# logger2.net
KiCad netlist of a schematic drawn in EAGLE
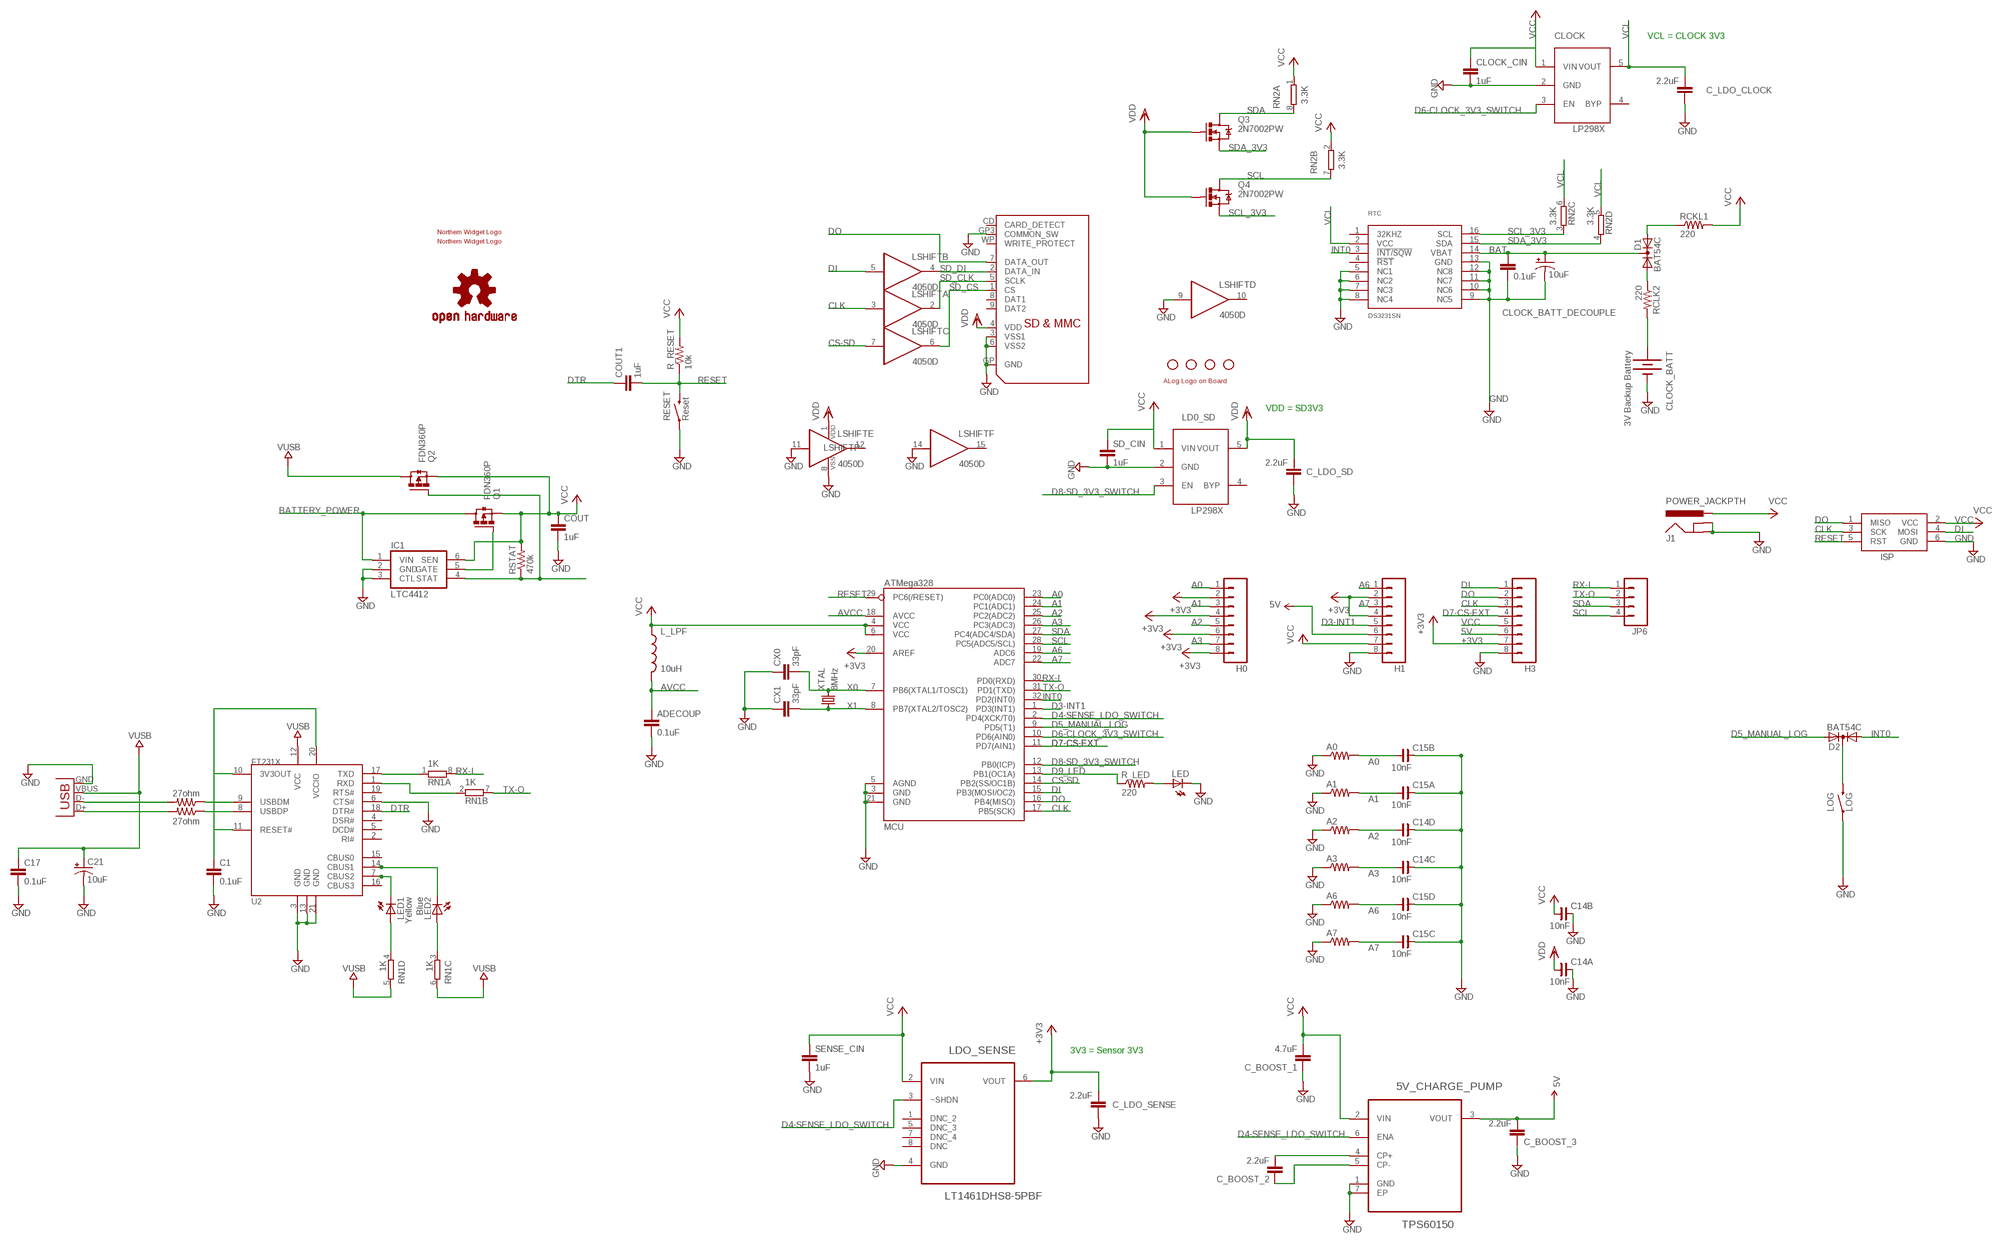
[diagram p0: schematic, sheet 1]

(export (version "E")
  (design (tool "Eeschema 10.0.6"))
  (components
    (comp (ref "5V_CHARGE_PUMP")
      (value "TPS60150")
      (footprint "eagle-import:SON65P200X200X80-7N")
      (fields (field (name "MPN") "TPS60150DRVR"))
      (libsource (lib "eagle-import") (part "TPS60150DRVR"))
    )
    (comp (ref "A0")
      (value "R-US_0207/10")
      (footprint "eagle-import:0207_10")
      (libsource (lib "eagle-import") (part "resistor_R-US_0207/10"))
    )
    (comp (ref "A1")
      (value "R-US_0207/10")
      (footprint "eagle-import:0207_10")
      (libsource (lib "eagle-import") (part "resistor_R-US_0207/10"))
    )
    (comp (ref "A2")
      (value "R-US_0207/10")
      (footprint "eagle-import:0207_10")
      (libsource (lib "eagle-import") (part "resistor_R-US_0207/10"))
    )
    (comp (ref "A3")
      (value "R-US_0207/10")
      (footprint "eagle-import:0207_10")
      (libsource (lib "eagle-import") (part "resistor_R-US_0207/10"))
    )
    (comp (ref "A6")
      (value "R-US_0207/10")
      (footprint "eagle-import:0207_10")
      (libsource (lib "eagle-import") (part "resistor_R-US_0207/10"))
    )
    (comp (ref "A7")
      (value "R-US_0207/10")
      (footprint "eagle-import:0207_10")
      (libsource (lib "eagle-import") (part "resistor_R-US_0207/10"))
    )
    (comp (ref "ADECOUP")
      (value "0.1uF")
      (footprint "eagle-import:C0603")
      (libsource (lib "eagle-import") (part "resistor_C-EUC0603"))
    )
    (comp (ref "C1")
      (value "0.1uF")
      (footprint "eagle-import:C0603")
      (libsource (lib "eagle-import") (part "resistor_C-EUC0603"))
    )
    (comp (ref "C14")
      (value "10nF")
      (footprint "eagle-import:CECJ-1206")
      (libsource (lib "eagle-import") (part "CCA_ECJ-1206"))
    )
    (comp (ref "C15")
      (value "10nF")
      (footprint "eagle-import:CECJ-1206")
      (libsource (lib "eagle-import") (part "CCA_ECJ-1206"))
    )
    (comp (ref "C17")
      (value "0.1uF")
      (footprint "eagle-import:C0603")
      (libsource (lib "eagle-import") (part "resistor_C-EUC0603"))
    )
    (comp (ref "C21")
      (value "10uF")
      (footprint "eagle-import:EIA3216")
      (libsource (lib "eagle-import") (part "CAP_POL1206"))
    )
    (comp (ref "CLOCK")
      (value "LP2985")
      (footprint "eagle-import:SOT23-5L")
      (libsource (lib "eagle-import") (part "LP298XS"))
    )
    (comp (ref "CLOCK_BATT")
      (value "3V Backup Battery")
      (footprint "eagle-import:BATTCON_12MM_PTH")
      (libsource (lib "eagle-import") (part "BATTERY12PTH"))
    )
    (comp (ref "CLOCK_BATT_DECOUP")
      (value "0.1uF")
      (footprint "eagle-import:C0603")
      (libsource (lib "eagle-import") (part "C-EUC0603"))
    )
    (comp (ref "CLOCK_BATT_DECOUPLE")
      (value "10uF")
      (footprint "eagle-import:EIA3216")
      (libsource (lib "eagle-import") (part "CAP_POL1206"))
    )
    (comp (ref "CLOCK_CIN")
      (value "1uF")
      (footprint "eagle-import:C0603")
      (libsource (lib "eagle-import") (part "C-EUC0603"))
    )
    (comp (ref "COUT")
      (value "1uF")
      (footprint "eagle-import:C0603")
      (libsource (lib "eagle-import") (part "C-EUC0603"))
    )
    (comp (ref "COUT1")
      (value "1uF")
      (footprint "eagle-import:C0603")
      (libsource (lib "eagle-import") (part "C-EUC0603"))
    )
    (comp (ref "CX0")
      (value "33pF")
      (footprint "eagle-import:C0603")
      (libsource (lib "eagle-import") (part "resistor_C-EUC0603"))
    )
    (comp (ref "CX1")
      (value "33pF")
      (footprint "eagle-import:C0603")
      (libsource (lib "eagle-import") (part "resistor_C-EUC0603"))
    )
    (comp (ref "C_BOOST_1")
      (value "4.7uF")
      (footprint "eagle-import:C0603")
      (libsource (lib "eagle-import") (part "resistor_C-EUC0603"))
    )
    (comp (ref "C_BOOST_2")
      (value "2.2uF")
      (footprint "eagle-import:C0603")
      (libsource (lib "eagle-import") (part "resistor_C-EUC0603"))
    )
    (comp (ref "C_BOOST_3")
      (value "2.2uF")
      (footprint "eagle-import:C0603")
      (libsource (lib "eagle-import") (part "resistor_C-EUC0603"))
    )
    (comp (ref "C_LDO_CLOCK")
      (value "2.2uF")
      (footprint "eagle-import:C0603")
      (libsource (lib "eagle-import") (part "resistor_C-EUC0603"))
    )
    (comp (ref "C_LDO_SD")
      (value "2.2uF")
      (footprint "eagle-import:C0603")
      (libsource (lib "eagle-import") (part "resistor_C-EUC0603"))
    )
    (comp (ref "C_LDO_SENSE")
      (value "2.2uF")
      (footprint "eagle-import:C0603")
      (libsource (lib "eagle-import") (part "resistor_C-EUC0603"))
    )
    (comp (ref "D+")
      (value "27ohm")
      (footprint "eagle-import:R0603")
      (libsource (lib "eagle-import") (part "R-US_R0603"))
    )
    (comp (ref "D-")
      (value "27ohm")
      (footprint "eagle-import:R0603")
      (libsource (lib "eagle-import") (part "R-US_R0603"))
    )
    (comp (ref "D1")
      (value "BAT54C")
      (footprint "eagle-import:SOT23C")
      (libsource (lib "eagle-import") (part "DIODE_AC-CA_"))
    )
    (comp (ref "D2")
      (value "BAT54C")
      (footprint "eagle-import:SOT23C")
      (libsource (lib "eagle-import") (part "DIODE_AC-CA_"))
    )
    (comp (ref "H0")
      (value "M083.5MM-8")
      (footprint "eagle-import:SCREWTERMINAL-3.5MM-8")
      (libsource (lib "eagle-import") (part "M083.5MM-8"))
    )
    (comp (ref "H1")
      (value "M083.5MM-8")
      (footprint "eagle-import:SCREWTERMINAL-3.5MM-8")
      (libsource (lib "eagle-import") (part "M083.5MM-8"))
    )
    (comp (ref "H3")
      (value "M083.5MM-8")
      (footprint "eagle-import:SCREWTERMINAL-3.5MM-8")
      (libsource (lib "eagle-import") (part "M083.5MM-8"))
    )
    (comp (ref "IC1")
      (value "LTC4412")
      (footprint "eagle-import:TSOT23-6")
      (libsource (lib "eagle-import") (part "LTC4412S6E"))
    )
    (comp (ref "ISP")
      (value "AVRISP-6")
      (footprint "eagle-import:AVRISP")
      (libsource (lib "eagle-import") (part "AVRISP-6"))
    )
    (comp (ref "J1")
      (value "POWER_JACKPTH")
      (footprint "eagle-import:POWER_JACK_PTH")
      (libsource (lib "eagle-import") (part "POWER_JACKPTH"))
    )
    (comp (ref "JP1")
      (value "STAND-OFF")
      (footprint "eagle-import:STAND-OFF")
      (libsource (lib "eagle-import") (part "STAND-OFF"))
    )
    (comp (ref "JP2")
      (value "STAND-OFF")
      (footprint "eagle-import:STAND-OFF")
      (libsource (lib "eagle-import") (part "STAND-OFF"))
    )
    (comp (ref "JP3")
      (value "STAND-OFF")
      (footprint "eagle-import:STAND-OFF")
      (libsource (lib "eagle-import") (part "STAND-OFF"))
    )
    (comp (ref "JP4")
      (value "STAND-OFF")
      (footprint "eagle-import:STAND-OFF")
      (libsource (lib "eagle-import") (part "STAND-OFF"))
    )
    (comp (ref "JP5")
      (value "USB-B")
      (footprint "eagle-import:USB-B-PTH")
      (libsource (lib "eagle-import") (part "USBPTH"))
    )
    (comp (ref "JP6")
      (value "M04SCREW")
      (footprint "eagle-import:SCREWTERMINAL-3.5MM-4")
      (libsource (lib "eagle-import") (part "M04SCREW"))
    )
    (comp (ref "LD0_SD")
      (value "LP2985")
      (footprint "eagle-import:SOT23-5L")
      (libsource (lib "eagle-import") (part "LP298XS"))
    )
    (comp (ref "LDO_SENSE")
      (value "LT1461DHS8-5PBF")
      (footprint "eagle-import:SOIC127P600X175-8N")
      (fields (field (name "MPN") "LT1461DHS8-5#PBF"))
      (libsource (lib "eagle-import") (part "LT1461DHS8-5PBF"))
    )
    (comp (ref "LED")
      (value "LED3MM")
      (footprint "eagle-import:LED3MM")
      (libsource (lib "eagle-import") (part "LED3MM"))
    )
    (comp (ref "LED1")
      (value "Yellow")
      (footprint "eagle-import:LED-0603")
      (libsource (lib "eagle-import") (part "SparkFun-LED_LED0603"))
    )
    (comp (ref "LED2")
      (value "Blue")
      (footprint "eagle-import:LED-0603")
      (libsource (lib "eagle-import") (part "SparkFun-LED_LED0603"))
    )
    (comp (ref "LOG")
      (value "LOG")
      (footprint "eagle-import:TACTILE-PTH")
      (libsource (lib "eagle-import") (part "SWITCH-MOMENTARY-2PTH"))
    )
    (comp (ref "LOGO1")
      (value "OSHW-LOGOM")
      (footprint "eagle-import:OSHW-LOGO-M")
      (libsource (lib "eagle-import") (part "OSHW-LOGOM"))
    )
    (comp (ref "LSHIFT")
      (value "4050D")
      (footprint "eagle-import:SO16")
      (libsource (lib "eagle-import") (part "4050D"))
    )
    (comp (ref "L_LPF")
      (value "10uH")
      (footprint "eagle-import:0805")
      (libsource (lib "eagle-import") (part "INDUCTOR0805"))
    )
    (comp (ref "MCU")
      (value "ATMega328")
      (footprint "eagle-import:TQFP32-08")
      (libsource (lib "eagle-import") (part "ATMEGA168"))
    )
    (comp (ref "Q1")
      (value "FDN360P")
      (footprint "eagle-import:SUPER-SOT3")
      (libsource (lib "eagle-import") (part "FDN360P"))
    )
    (comp (ref "Q2")
      (value "FDN360P")
      (footprint "eagle-import:SUPER-SOT3")
      (libsource (lib "eagle-import") (part "FDN360P"))
    )
    (comp (ref "Q3")
      (value "2N7002PW")
      (footprint "eagle-import:SOT323")
      (libsource (lib "eagle-import") (part "MOSFET-NCHANNELSOT323"))
    )
    (comp (ref "Q4")
      (value "2N7002PW")
      (footprint "eagle-import:SOT323")
      (libsource (lib "eagle-import") (part "MOSFET-NCHANNELSOT323"))
    )
    (comp (ref "RCKL1")
      (value "220")
      (footprint "eagle-import:R0603")
      (libsource (lib "eagle-import") (part "R-US_R0603"))
    )
    (comp (ref "RCLK2")
      (value "220")
      (footprint "eagle-import:R0603")
      (libsource (lib "eagle-import") (part "R-US_R0603"))
    )
    (comp (ref "RESET")
      (value "Reset")
      (footprint "eagle-import:TACTILE-PTH")
      (libsource (lib "eagle-import") (part "SWITCH-MOMENTARY-2PTH"))
    )
    (comp (ref "RN1")
      (value "1K")
      (footprint "eagle-import:0603-ARC")
      (libsource (lib "eagle-import") (part "4R-N0603-ARC"))
    )
    (comp (ref "RN2")
      (value "3.3K")
      (footprint "eagle-import:0603-ARC")
      (libsource (lib "eagle-import") (part "4R-N0603-ARC"))
    )
    (comp (ref "RSTAT")
      (value "470k")
      (footprint "eagle-import:R0603")
      (libsource (lib "eagle-import") (part "R-US_R0603"))
    )
    (comp (ref "RTC")
      (value "DS3231SN")
      (footprint "eagle-import:SO16W")
      (libsource (lib "eagle-import") (part "DS3231SN"))
    )
    (comp (ref "R_LED")
      (value "220")
      (footprint "eagle-import:R0603")
      (libsource (lib "eagle-import") (part "resistor_R-US_R0603"))
    )
    (comp (ref "R_RESET")
      (value "10k")
      (footprint "eagle-import:R0603")
      (libsource (lib "eagle-import") (part "R-US_R0603"))
    )
    (comp (ref "SD")
      (value "SDMMC06132")
      (footprint "eagle-import:06132")
      (libsource (lib "eagle-import") (part "SDMMC06132"))
    )
    (comp (ref "SD_CIN")
      (value "1uF")
      (footprint "eagle-import:C0603")
      (libsource (lib "eagle-import") (part "C-EUC0603"))
    )
    (comp (ref "SENSE_CIN")
      (value "1uF")
      (footprint "eagle-import:C0603")
      (libsource (lib "eagle-import") (part "C-EUC0603"))
    )
    (comp (ref "U$1")
      (value "NWLOGO")
      (footprint "eagle-import:NWLOGO")
      (libsource (lib "eagle-import") (part "NWLOGO"))
    )
    (comp (ref "U$2")
      (value "ALOG_LOGO_V1_5.5MM")
      (footprint "eagle-import:ALOG_LOGO_V1_SMALL")
      (libsource (lib "eagle-import") (part "ALOG_LOGO_V1_5.5MM"))
    )
    (comp (ref "U$3")
      (value "NWLOGO_MED")
      (footprint "eagle-import:NWLOGO_MED")
      (libsource (lib "eagle-import") (part "NWLOGO_MED"))
    )
    (comp (ref "U2")
      (value "FT231X-Q")
      (footprint "eagle-import:QFN20")
      (libsource (lib "eagle-import") (part "FT231X-Q"))
    )
    (comp (ref "XTAL")
      (value "8MHz")
      (footprint "eagle-import:HC49U-V")
      (libsource (lib "eagle-import") (part "CRYSTALHC49UV"))
    )
  )
  (nets
    (net (code "1") (name "+3V3") (class "Default")
      (node (ref "C_LDO_SENSE") (pin "2") (pinfunction "2_2") (pintype "passive"))
      (node (ref "H0") (pin "2") (pinfunction "2_2") (pintype "passive"))
      (node (ref "H0") (pin "4") (pinfunction "4_4") (pintype "passive"))
      (node (ref "H0") (pin "6") (pinfunction "6_6") (pintype "passive"))
      (node (ref "H0") (pin "8") (pinfunction "8_8") (pintype "passive"))
      (node (ref "H1") (pin "2") (pinfunction "2_2") (pintype "passive"))
      (node (ref "H1") (pin "4") (pinfunction "4_4") (pintype "passive"))
      (node (ref "H3") (pin "7") (pinfunction "7_7") (pintype "passive"))
      (node (ref "LDO_SENSE") (pin "6") (pinfunction "VOUT_6") (pintype "output"))
      (node (ref "MCU") (pin "20") (pinfunction "AREF_20") (pintype "bidirectional"))
    )
    (net (code "2") (name "/A0") (class "Default")
      (node (ref "A0") (pin "2") (pinfunction "2_2") (pintype "passive"))
      (node (ref "C15") (pin "B1") (pinfunction "1_B1") (pintype "passive"))
      (node (ref "H0") (pin "1") (pinfunction "1_1") (pintype "passive"))
      (node (ref "MCU") (pin "23") (pinfunction "PC0(ADC0)_23") (pintype "bidirectional"))
    )
    (net (code "3") (name "/A1") (class "Default")
      (node (ref "A1") (pin "2") (pinfunction "2_2") (pintype "passive"))
      (node (ref "C15") (pin "A1") (pinfunction "1_A1") (pintype "passive"))
      (node (ref "H0") (pin "3") (pinfunction "3_3") (pintype "passive"))
      (node (ref "MCU") (pin "24") (pinfunction "PC1(ADC1)_24") (pintype "bidirectional"))
    )
    (net (code "4") (name "/A2") (class "Default")
      (node (ref "A2") (pin "2") (pinfunction "2_2") (pintype "passive"))
      (node (ref "C14") (pin "D1") (pinfunction "1_D1") (pintype "passive"))
      (node (ref "H0") (pin "5") (pinfunction "5_5") (pintype "passive"))
      (node (ref "MCU") (pin "25") (pinfunction "PC2(ADC2)_25") (pintype "bidirectional"))
    )
    (net (code "5") (name "/A3") (class "Default")
      (node (ref "A3") (pin "2") (pinfunction "2_2") (pintype "passive"))
      (node (ref "C14") (pin "C1") (pinfunction "1_C1") (pintype "passive"))
      (node (ref "H0") (pin "7") (pinfunction "7_7") (pintype "passive"))
      (node (ref "MCU") (pin "26") (pinfunction "PC3(ADC3)_26") (pintype "bidirectional"))
    )
    (net (code "6") (name "/A6") (class "Default")
      (node (ref "A6") (pin "2") (pinfunction "2_2") (pintype "passive"))
      (node (ref "C15") (pin "D1") (pinfunction "1_D1") (pintype "passive"))
      (node (ref "H1") (pin "1") (pinfunction "1_1") (pintype "passive"))
      (node (ref "MCU") (pin "19") (pinfunction "ADC6_19") (pintype "bidirectional"))
    )
    (net (code "7") (name "/A7") (class "Default")
      (node (ref "A7") (pin "2") (pinfunction "2_2") (pintype "passive"))
      (node (ref "C15") (pin "C1") (pinfunction "1_C1") (pintype "passive"))
      (node (ref "H1") (pin "3") (pinfunction "3_3") (pintype "passive"))
      (node (ref "MCU") (pin "22") (pinfunction "ADC7_22") (pintype "bidirectional"))
    )
    (net (code "8") (name "/AVCC") (class "Default")
      (node (ref "ADECOUP") (pin "1") (pinfunction "1_1") (pintype "passive"))
      (node (ref "L_LPF") (pin "2") (pinfunction "2_2") (pintype "passive"))
      (node (ref "MCU") (pin "18") (pinfunction "AVCC_18") (pintype "bidirectional"))
    )
    (net (code "9") (name "/BAT") (class "Default")
      (node (ref "CLOCK_BATT_DECOUP") (pin "1") (pinfunction "1_1") (pintype "passive"))
      (node (ref "CLOCK_BATT_DECOUPLE") (pin "A") (pinfunction "+_A") (pintype "passive"))
      (node (ref "D1") (pin "3") (pinfunction "K_3") (pintype "passive"))
      (node (ref "RTC") (pin "14") (pinfunction "VBAT_14") (pintype "bidirectional"))
    )
    (net (code "10") (name "/BATTERY_POWER") (class "Default")
      (node (ref "IC1") (pin "1") (pinfunction "VIN_1") (pintype "input"))
      (node (ref "Q1") (pin "3") (pinfunction "D_3") (pintype "passive"))
    )
    (net (code "11") (name "/CLK") (class "Default")
      (node (ref "H3") (pin "3") (pinfunction "3_3") (pintype "passive"))
      (node (ref "ISP") (pin "3") (pinfunction "SCK_3") (pintype "output"))
      (node (ref "LSHIFT") (pin "3") (pinfunction "I_3") (pintype "input"))
      (node (ref "MCU") (pin "17") (pinfunction "PB5(SCK)_17") (pintype "bidirectional"))
    )
    (net (code "12") (name "/CS-SD") (class "Default")
      (node (ref "LSHIFT") (pin "7") (pinfunction "I_7") (pintype "input"))
      (node (ref "MCU") (pin "14") (pinfunction "PB2(SS/OC1B)_14") (pintype "bidirectional"))
    )
    (net (code "13") (name "/D3-INT1") (class "Default")
      (node (ref "H1") (pin "5") (pinfunction "5_5") (pintype "passive"))
      (node (ref "MCU") (pin "1") (pinfunction "PD3(INT1)_1") (pintype "bidirectional"))
    )
    (net (code "14") (name "/D4-SENSE_LDO_SWITCH") (class "Default")
      (node (ref "5V_CHARGE_PUMP") (pin "6") (pinfunction "ENA_6") (pintype "input"))
      (node (ref "LDO_SENSE") (pin "3") (pinfunction "~{SHDN}_3") (pintype "input"))
      (node (ref "MCU") (pin "2") (pinfunction "PD4(XCK/T0)_2") (pintype "bidirectional"))
    )
    (net (code "15") (name "/D5_MANUAL_LOG") (class "Default")
      (node (ref "D2") (pin "2") (pinfunction "A2_2") (pintype "passive"))
      (node (ref "MCU") (pin "9") (pinfunction "PD5(T1)_9") (pintype "bidirectional"))
    )
    (net (code "16") (name "/D6-CLOCK_3V3_SWITCH") (class "Default")
      (node (ref "CLOCK") (pin "3") (pinfunction "EN_3") (pintype "bidirectional"))
      (node (ref "MCU") (pin "10") (pinfunction "PD6(AIN0)_10") (pintype "bidirectional"))
    )
    (net (code "17") (name "/D7-CS-EXT") (class "Default")
      (node (ref "H3") (pin "4") (pinfunction "4_4") (pintype "passive"))
      (node (ref "MCU") (pin "11") (pinfunction "PD7(AIN1)_11") (pintype "bidirectional"))
    )
    (net (code "18") (name "/D8-SD_3V3_SWITCH") (class "Default")
      (node (ref "LD0_SD") (pin "3") (pinfunction "EN_3") (pintype "bidirectional"))
      (node (ref "MCU") (pin "12") (pinfunction "PB0(ICP)_12") (pintype "bidirectional"))
    )
    (net (code "19") (name "/D9_LED") (class "Default")
      (node (ref "MCU") (pin "13") (pinfunction "PB1(OC1A)_13") (pintype "bidirectional"))
      (node (ref "R_LED") (pin "1") (pinfunction "1_1") (pintype "passive"))
    )
    (net (code "20") (name "/DI") (class "Default")
      (node (ref "H3") (pin "1") (pinfunction "1_1") (pintype "passive"))
      (node (ref "ISP") (pin "4") (pinfunction "MOSI_4") (pintype "output"))
      (node (ref "LSHIFT") (pin "5") (pinfunction "I_5") (pintype "input"))
      (node (ref "MCU") (pin "15") (pinfunction "PB3(MOSI/OC2)_15") (pintype "bidirectional"))
    )
    (net (code "21") (name "/DO") (class "Default")
      (node (ref "H3") (pin "2") (pinfunction "2_2") (pintype "passive"))
      (node (ref "ISP") (pin "1") (pinfunction "MISO_1") (pintype "input"))
      (node (ref "MCU") (pin "16") (pinfunction "PB4(MISO)_16") (pintype "bidirectional"))
      (node (ref "SD") (pin "7") (pinfunction "DATA_OUT_7") (pintype "output"))
    )
    (net (code "22") (name "/DTR") (class "Default")
      (node (ref "COUT1") (pin "1") (pinfunction "1_1") (pintype "passive"))
      (node (ref "U2") (pin "18") (pinfunction "DTR#_18") (pintype "bidirectional"))
    )
    (net (code "23") (name "/INT0") (class "Default")
      (node (ref "D2") (pin "1") (pinfunction "A1_1") (pintype "passive"))
      (node (ref "MCU") (pin "32") (pinfunction "PD2(INT0)_32") (pintype "bidirectional"))
      (node (ref "RTC") (pin "3") (pinfunction "~{INT/SQW}_3") (pintype "bidirectional"))
    )
    (net (code "24") (name "/RESET") (class "Default")
      (node (ref "COUT1") (pin "2") (pinfunction "2_2") (pintype "passive"))
      (node (ref "ISP") (pin "5") (pinfunction "RST_5") (pintype "output"))
      (node (ref "MCU") (pin "29") (pinfunction "PC6(/RESET)_29") (pintype "bidirectional"))
      (node (ref "RESET") (pin "3") (pinfunction "2_3") (pintype "passive"))
      (node (ref "R_RESET") (pin "1") (pinfunction "1_1") (pintype "passive"))
    )
    (net (code "25") (name "/RX-I") (class "Default")
      (node (ref "JP6") (pin "1") (pinfunction "1_1") (pintype "passive"))
      (node (ref "MCU") (pin "30") (pinfunction "PD0(RXD)_30") (pintype "bidirectional"))
      (node (ref "RN1") (pin "8") (pinfunction "2_8") (pintype "passive"))
    )
    (net (code "26") (name "/SCL") (class "Default")
      (node (ref "JP6") (pin "4") (pinfunction "4_4") (pintype "passive"))
      (node (ref "MCU") (pin "28") (pinfunction "PC5(ADC5/SCL)_28") (pintype "bidirectional"))
      (node (ref "Q4") (pin "3") (pinfunction "D_3") (pintype "passive"))
      (node (ref "RN2") (pin "7") (pinfunction "2_7") (pintype "passive"))
    )
    (net (code "27") (name "/SCL_3V3") (class "Default")
      (node (ref "Q4") (pin "2") (pinfunction "S_2") (pintype "passive"))
      (node (ref "RN2") (pin "3") (pinfunction "1_3") (pintype "passive"))
      (node (ref "RTC") (pin "16") (pinfunction "SCL_16") (pintype "bidirectional"))
    )
    (net (code "28") (name "/SDA") (class "Default")
      (node (ref "JP6") (pin "3") (pinfunction "3_3") (pintype "passive"))
      (node (ref "MCU") (pin "27") (pinfunction "PC4(ADC4/SDA)_27") (pintype "bidirectional"))
      (node (ref "Q3") (pin "3") (pinfunction "D_3") (pintype "passive"))
      (node (ref "RN2") (pin "8") (pinfunction "2_8") (pintype "passive"))
    )
    (net (code "29") (name "/SDA_3V3") (class "Default")
      (node (ref "Q3") (pin "2") (pinfunction "S_2") (pintype "passive"))
      (node (ref "RN2") (pin "4") (pinfunction "1_4") (pintype "passive"))
      (node (ref "RTC") (pin "15") (pinfunction "SDA_15") (pintype "bidirectional"))
    )
    (net (code "30") (name "/SD_CLK") (class "Default")
      (node (ref "LSHIFT") (pin "2") (pinfunction "O_2") (pintype "output"))
      (node (ref "SD") (pin "5") (pinfunction "SCLK_5") (pintype "input"))
    )
    (net (code "31") (name "/SD_CS") (class "Default")
      (node (ref "LSHIFT") (pin "6") (pinfunction "O_6") (pintype "output"))
      (node (ref "SD") (pin "1") (pinfunction "CS_1") (pintype "input"))
    )
    (net (code "32") (name "/SD_DI") (class "Default")
      (node (ref "LSHIFT") (pin "4") (pinfunction "O_4") (pintype "output"))
      (node (ref "SD") (pin "2") (pinfunction "DATA_IN_2") (pintype "input"))
    )
    (net (code "33") (name "/TX-O") (class "Default")
      (node (ref "JP6") (pin "2") (pinfunction "2_2") (pintype "passive"))
      (node (ref "MCU") (pin "31") (pinfunction "PD1(TXD)_31") (pintype "bidirectional"))
      (node (ref "RN1") (pin "7") (pinfunction "2_7") (pintype "passive"))
    )
    (net (code "34") (name "/VCL") (class "Default")
      (node (ref "CLOCK") (pin "5") (pinfunction "VOUT_5") (pintype "bidirectional"))
      (node (ref "C_LDO_CLOCK") (pin "2") (pinfunction "2_2") (pintype "passive"))
      (node (ref "RN2") (pin "5") (pinfunction "2_5") (pintype "passive"))
      (node (ref "RN2") (pin "6") (pinfunction "2_6") (pintype "passive"))
      (node (ref "RTC") (pin "2") (pinfunction "VCC_2") (pintype "bidirectional"))
    )
    (net (code "35") (name "/X0") (class "Default")
      (node (ref "CX0") (pin "2") (pinfunction "2_2") (pintype "passive"))
      (node (ref "MCU") (pin "7") (pinfunction "PB6(XTAL1/TOSC1)_7") (pintype "bidirectional"))
      (node (ref "XTAL") (pin "2") (pinfunction "2_2") (pintype "passive"))
    )
    (net (code "36") (name "/X1") (class "Default")
      (node (ref "CX1") (pin "2") (pinfunction "2_2") (pintype "passive"))
      (node (ref "MCU") (pin "8") (pinfunction "PB7(XTAL2/TOSC2)_8") (pintype "bidirectional"))
      (node (ref "XTAL") (pin "1") (pinfunction "1_1") (pintype "passive"))
    )
    (net (code "37") (name "5V") (class "Default")
      (node (ref "5V_CHARGE_PUMP") (pin "3") (pinfunction "VOUT_3") (pintype "output"))
      (node (ref "C_BOOST_3") (pin "2") (pinfunction "2_2") (pintype "passive"))
      (node (ref "H1") (pin "6") (pinfunction "6_6") (pintype "passive"))
      (node (ref "H3") (pin "6") (pinfunction "6_6") (pintype "passive"))
    )
    (net (code "38") (name "GND") (class "Default")
      (node (ref "5V_CHARGE_PUMP") (pin "1") (pinfunction "GND_1") (pintype "passive"))
      (node (ref "5V_CHARGE_PUMP") (pin "7") (pinfunction "EP_7") (pintype "passive"))
      (node (ref "A0") (pin "1") (pinfunction "1_1") (pintype "passive"))
      (node (ref "A1") (pin "1") (pinfunction "1_1") (pintype "passive"))
      (node (ref "A2") (pin "1") (pinfunction "1_1") (pintype "passive"))
      (node (ref "A3") (pin "1") (pinfunction "1_1") (pintype "passive"))
      (node (ref "A6") (pin "1") (pinfunction "1_1") (pintype "passive"))
      (node (ref "A7") (pin "1") (pinfunction "1_1") (pintype "passive"))
      (node (ref "ADECOUP") (pin "2") (pinfunction "2_2") (pintype "passive"))
      (node (ref "C1") (pin "2") (pinfunction "2_2") (pintype "passive"))
      (node (ref "C14") (pin "A2") (pinfunction "2_A2") (pintype "passive"))
      (node (ref "C14") (pin "B2") (pinfunction "2_B2") (pintype "passive"))
      (node (ref "C14") (pin "C2") (pinfunction "2_C2") (pintype "passive"))
      (node (ref "C14") (pin "D2") (pinfunction "2_D2") (pintype "passive"))
      (node (ref "C15") (pin "A2") (pinfunction "2_A2") (pintype "passive"))
      (node (ref "C15") (pin "B2") (pinfunction "2_B2") (pintype "passive"))
      (node (ref "C15") (pin "C2") (pinfunction "2_C2") (pintype "passive"))
      (node (ref "C15") (pin "D2") (pinfunction "2_D2") (pintype "passive"))
      (node (ref "C17") (pin "2") (pinfunction "2_2") (pintype "passive"))
      (node (ref "C21") (pin "C") (pinfunction "-_C") (pintype "passive"))
      (node (ref "CLOCK") (pin "2") (pinfunction "GND_2") (pintype "bidirectional"))
      (node (ref "CLOCK_BATT") (pin "GND") (pinfunction "-_GND") (pintype "power_in"))
      (node (ref "CLOCK_BATT_DECOUP") (pin "2") (pinfunction "2_2") (pintype "passive"))
      (node (ref "CLOCK_BATT_DECOUPLE") (pin "C") (pinfunction "-_C") (pintype "passive"))
      (node (ref "CLOCK_CIN") (pin "2") (pinfunction "2_2") (pintype "passive"))
      (node (ref "COUT") (pin "2") (pinfunction "2_2") (pintype "passive"))
      (node (ref "CX0") (pin "1") (pinfunction "1_1") (pintype "passive"))
      (node (ref "CX1") (pin "1") (pinfunction "1_1") (pintype "passive"))
      (node (ref "C_BOOST_1") (pin "1") (pinfunction "1_1") (pintype "passive"))
      (node (ref "C_BOOST_3") (pin "1") (pinfunction "1_1") (pintype "passive"))
      (node (ref "C_LDO_CLOCK") (pin "1") (pinfunction "1_1") (pintype "passive"))
      (node (ref "C_LDO_SD") (pin "1") (pinfunction "1_1") (pintype "passive"))
      (node (ref "C_LDO_SENSE") (pin "1") (pinfunction "1_1") (pintype "passive"))
      (node (ref "H1") (pin "8") (pinfunction "8_8") (pintype "passive"))
      (node (ref "H3") (pin "8") (pinfunction "8_8") (pintype "passive"))
      (node (ref "IC1") (pin "2") (pinfunction "GND_2") (pintype "passive"))
      (node (ref "IC1") (pin "3") (pinfunction "CTL_3") (pintype "input"))
      (node (ref "ISP") (pin "6") (pinfunction "GND_6") (pintype "power_in"))
      (node (ref "J1") (pin "GND") (pinfunction "GND_GND") (pintype "bidirectional"))
      (node (ref "J1") (pin "GNDBREAK") (pinfunction "GNDBREAK_GNDBREAK") (pintype "bidirectional"))
      (node (ref "JP5") (pin "GND") (pinfunction "GND_GND") (pintype "bidirectional"))
      (node (ref "LD0_SD") (pin "2") (pinfunction "GND_2") (pintype "bidirectional"))
      (node (ref "LDO_SENSE") (pin "4") (pinfunction "GND_4") (pintype "passive"))
      (node (ref "LED") (pin "K") (pinfunction "C_K") (pintype "passive"))
      (node (ref "LOG") (pin "1") (pinfunction "1_1") (pintype "passive"))
      (node (ref "LSHIFT") (pin "11") (pinfunction "I_11") (pintype "input"))
      (node (ref "LSHIFT") (pin "14") (pinfunction "I_14") (pintype "input"))
      (node (ref "LSHIFT") (pin "8") (pinfunction "VSS_8") (pintype "power_in"))
      (node (ref "LSHIFT") (pin "9") (pinfunction "I_9") (pintype "input"))
      (node (ref "MCU") (pin "21") (pinfunction "GND_21") (pintype "bidirectional"))
      (node (ref "MCU") (pin "3") (pinfunction "GND_3") (pintype "bidirectional"))
      (node (ref "MCU") (pin "5") (pinfunction "AGND_5") (pintype "bidirectional"))
      (node (ref "RESET") (pin "1") (pinfunction "1_1") (pintype "passive"))
      (node (ref "RTC") (pin "10") (pinfunction "NC6_10") (pintype "bidirectional"))
      (node (ref "RTC") (pin "11") (pinfunction "NC7_11") (pintype "bidirectional"))
      (node (ref "RTC") (pin "12") (pinfunction "NC8_12") (pintype "bidirectional"))
      (node (ref "RTC") (pin "13") (pinfunction "GND_13") (pintype "bidirectional"))
      (node (ref "RTC") (pin "5") (pinfunction "NC1_5") (pintype "bidirectional"))
      (node (ref "RTC") (pin "6") (pinfunction "NC2_6") (pintype "bidirectional"))
      (node (ref "RTC") (pin "7") (pinfunction "NC3_7") (pintype "bidirectional"))
      (node (ref "RTC") (pin "8") (pinfunction "NC4_8") (pintype "bidirectional"))
      (node (ref "RTC") (pin "9") (pinfunction "NC5_9") (pintype "bidirectional"))
      (node (ref "SD") (pin "3") (pinfunction "VSS1_3") (pintype "power_in"))
      (node (ref "SD") (pin "6") (pinfunction "VSS2_6") (pintype "power_in"))
      (node (ref "SD") (pin "GP") (pinfunction "GND_GP") (pintype "power_in"))
      (node (ref "SD") (pin "GP3") (pinfunction "COMMON_SW_GP3") (pintype "passive"))
      (node (ref "SD_CIN") (pin "2") (pinfunction "2_2") (pintype "passive"))
      (node (ref "SENSE_CIN") (pin "2") (pinfunction "2_2") (pintype "passive"))
      (node (ref "U2") (pin "13") (pinfunction "GND_13") (pintype "bidirectional"))
      (node (ref "U2") (pin "21") (pinfunction "GND_21") (pintype "bidirectional"))
      (node (ref "U2") (pin "3") (pinfunction "GND_3") (pintype "bidirectional"))
      (node (ref "U2") (pin "6") (pinfunction "CTS#_6") (pintype "bidirectional"))
    )
    (net (code "39") (name "Net-(5V_CHARGE_PUMP-CP+)") (class "Default")
      (node (ref "5V_CHARGE_PUMP") (pin "4") (pinfunction "CP+_4") (pintype "passive"))
      (node (ref "C_BOOST_2") (pin "2") (pinfunction "2_2") (pintype "passive"))
    )
    (net (code "40") (name "Net-(5V_CHARGE_PUMP-CP-)") (class "Default")
      (node (ref "5V_CHARGE_PUMP") (pin "5") (pinfunction "CP-_5") (pintype "passive"))
      (node (ref "C_BOOST_2") (pin "1") (pinfunction "1_1") (pintype "passive"))
    )
    (net (code "41") (name "Net-(CLOCK_BATT-+)") (class "Default")
      (node (ref "CLOCK_BATT") (pin "VCC@1") (pinfunction "+_VCC@1") (pintype "power_in"))
      (node (ref "RCLK2") (pin "2") (pinfunction "2_2") (pintype "passive"))
    )
    (net (code "42") (name "Net-(D+-Pad2)") (class "Default")
      (node (ref "D+") (pin "2") (pinfunction "2_2") (pintype "passive"))
      (node (ref "JP5") (pin "D+") (pinfunction "D+_D+") (pintype "bidirectional"))
    )
    (net (code "43") (name "Net-(D--Pad2)") (class "Default")
      (node (ref "D-") (pin "2") (pinfunction "2_2") (pintype "passive"))
      (node (ref "JP5") (pin "D-") (pinfunction "D-_D-") (pintype "bidirectional"))
    )
    (net (code "44") (name "Net-(D1-A1)") (class "Default")
      (node (ref "D1") (pin "1") (pinfunction "A1_1") (pintype "passive"))
      (node (ref "RCLK2") (pin "1") (pinfunction "1_1") (pintype "passive"))
    )
    (net (code "45") (name "Net-(D1-A2)") (class "Default")
      (node (ref "D1") (pin "2") (pinfunction "A2_2") (pintype "passive"))
      (node (ref "RCKL1") (pin "1") (pinfunction "1_1") (pintype "passive"))
    )
    (net (code "46") (name "Net-(D2-K)") (class "Default")
      (node (ref "D2") (pin "3") (pinfunction "K_3") (pintype "passive"))
      (node (ref "LOG") (pin "3") (pinfunction "2_3") (pintype "passive"))
    )
    (net (code "47") (name "Net-(IC1-GATE)") (class "Default")
      (node (ref "IC1") (pin "5") (pinfunction "GATE_5") (pintype "output"))
      (node (ref "Q1") (pin "1") (pinfunction "G_1") (pintype "passive"))
    )
    (net (code "48") (name "Net-(IC1-STAT)") (class "Default")
      (node (ref "IC1") (pin "4") (pinfunction "STAT_4") (pintype "open_collector"))
      (node (ref "Q2") (pin "1") (pinfunction "G_1") (pintype "passive"))
      (node (ref "RSTAT") (pin "1") (pinfunction "1_1") (pintype "passive"))
    )
    (net (code "49") (name "Net-(LED-PadA)") (class "Default")
      (node (ref "LED") (pin "A") (pinfunction "A_A") (pintype "passive"))
      (node (ref "R_LED") (pin "2") (pinfunction "2_2") (pintype "passive"))
    )
    (net (code "50") (name "Net-(RN1B-1)") (class "Default")
      (node (ref "RN1") (pin "2") (pinfunction "1_2") (pintype "passive"))
      (node (ref "U2") (pin "1") (pinfunction "RXD_1") (pintype "bidirectional"))
    )
    (net (code "51") (name "Net-(RN1C-1)") (class "Default")
      (node (ref "LED2") (pin "A") (pinfunction "A_A") (pintype "passive"))
      (node (ref "RN1") (pin "3") (pinfunction "1_3") (pintype "passive"))
    )
    (net (code "52") (name "Net-(RN1D-1)") (class "Default")
      (node (ref "LED1") (pin "A") (pinfunction "A_A") (pintype "passive"))
      (node (ref "RN1") (pin "4") (pinfunction "1_4") (pintype "passive"))
    )
    (net (code "53") (name "Net-(U2-3V3OUT)") (class "Default")
      (node (ref "C1") (pin "1") (pinfunction "1_1") (pintype "passive"))
      (node (ref "U2") (pin "10") (pinfunction "3V3OUT_10") (pintype "bidirectional"))
      (node (ref "U2") (pin "11") (pinfunction "RESET#_11") (pintype "bidirectional"))
      (node (ref "U2") (pin "20") (pinfunction "VCCIO_20") (pintype "bidirectional"))
    )
    (net (code "54") (name "Net-(U2-CBUS1)") (class "Default")
      (node (ref "LED2") (pin "C") (pinfunction "C_C") (pintype "passive"))
      (node (ref "U2") (pin "14") (pinfunction "CBUS1_14") (pintype "bidirectional"))
    )
    (net (code "55") (name "Net-(U2-CBUS2)") (class "Default")
      (node (ref "LED1") (pin "C") (pinfunction "C_C") (pintype "passive"))
      (node (ref "U2") (pin "7") (pinfunction "CBUS2_7") (pintype "bidirectional"))
    )
    (net (code "56") (name "Net-(U2-TXD)") (class "Default")
      (node (ref "RN1") (pin "1") (pinfunction "1_1") (pintype "passive"))
      (node (ref "U2") (pin "17") (pinfunction "TXD_17") (pintype "bidirectional"))
    )
    (net (code "57") (name "Net-(U2-USBDM)") (class "Default")
      (node (ref "D-") (pin "1") (pinfunction "1_1") (pintype "passive"))
      (node (ref "U2") (pin "9") (pinfunction "USBDM_9") (pintype "bidirectional"))
    )
    (net (code "58") (name "Net-(U2-USBDP)") (class "Default")
      (node (ref "D+") (pin "1") (pinfunction "1_1") (pintype "passive"))
      (node (ref "U2") (pin "8") (pinfunction "USBDP_8") (pintype "bidirectional"))
    )
    (net (code "59") (name "VCC") (class "Default")
      (node (ref "5V_CHARGE_PUMP") (pin "2") (pinfunction "VIN_2") (pintype "power_in"))
      (node (ref "C14") (pin "B1") (pinfunction "1_B1") (pintype "passive"))
      (node (ref "CLOCK") (pin "1") (pinfunction "VIN_1") (pintype "bidirectional"))
      (node (ref "CLOCK_CIN") (pin "1") (pinfunction "1_1") (pintype "passive"))
      (node (ref "COUT") (pin "1") (pinfunction "1_1") (pintype "passive"))
      (node (ref "C_BOOST_1") (pin "2") (pinfunction "2_2") (pintype "passive"))
      (node (ref "H1") (pin "7") (pinfunction "7_7") (pintype "passive"))
      (node (ref "H3") (pin "5") (pinfunction "5_5") (pintype "passive"))
      (node (ref "IC1") (pin "6") (pinfunction "SEN_6") (pintype "input"))
      (node (ref "ISP") (pin "2") (pinfunction "VCC_2") (pintype "power_in"))
      (node (ref "J1") (pin "PWR") (pinfunction "PWR_PWR") (pintype "bidirectional"))
      (node (ref "LD0_SD") (pin "1") (pinfunction "VIN_1") (pintype "bidirectional"))
      (node (ref "LDO_SENSE") (pin "2") (pinfunction "VIN_2") (pintype "power_in"))
      (node (ref "L_LPF") (pin "1") (pinfunction "1_1") (pintype "passive"))
      (node (ref "MCU") (pin "4") (pinfunction "VCC_4") (pintype "bidirectional"))
      (node (ref "MCU") (pin "6") (pinfunction "VCC_6") (pintype "bidirectional"))
      (node (ref "Q1") (pin "2") (pinfunction "S_2") (pintype "passive"))
      (node (ref "Q2") (pin "2") (pinfunction "S_2") (pintype "passive"))
      (node (ref "RCKL1") (pin "2") (pinfunction "2_2") (pintype "passive"))
      (node (ref "RN2") (pin "1") (pinfunction "1_1") (pintype "passive"))
      (node (ref "RN2") (pin "2") (pinfunction "1_2") (pintype "passive"))
      (node (ref "RSTAT") (pin "2") (pinfunction "2_2") (pintype "passive"))
      (node (ref "R_RESET") (pin "2") (pinfunction "2_2") (pintype "passive"))
      (node (ref "SD_CIN") (pin "1") (pinfunction "1_1") (pintype "passive"))
      (node (ref "SENSE_CIN") (pin "1") (pinfunction "1_1") (pintype "passive"))
    )
    (net (code "60") (name "VDD") (class "Default")
      (node (ref "C14") (pin "A1") (pinfunction "1_A1") (pintype "passive"))
      (node (ref "C_LDO_SD") (pin "2") (pinfunction "2_2") (pintype "passive"))
      (node (ref "LD0_SD") (pin "5") (pinfunction "VOUT_5") (pintype "bidirectional"))
      (node (ref "LSHIFT") (pin "1") (pinfunction "VDD_1") (pintype "power_in"))
      (node (ref "Q3") (pin "1") (pinfunction "G_1") (pintype "passive"))
      (node (ref "Q4") (pin "1") (pinfunction "G_1") (pintype "passive"))
      (node (ref "SD") (pin "4") (pinfunction "VDD_4") (pintype "power_in"))
    )
    (net (code "61") (name "VUSB") (class "Default")
      (node (ref "C17") (pin "1") (pinfunction "1_1") (pintype "passive"))
      (node (ref "C21") (pin "A") (pinfunction "+_A") (pintype "passive"))
      (node (ref "JP5") (pin "VBUS") (pinfunction "VBUS_VBUS") (pintype "bidirectional"))
      (node (ref "Q2") (pin "3") (pinfunction "D_3") (pintype "passive"))
      (node (ref "RN1") (pin "5") (pinfunction "2_5") (pintype "passive"))
      (node (ref "RN1") (pin "6") (pinfunction "2_6") (pintype "passive"))
      (node (ref "U2") (pin "12") (pinfunction "VCC_12") (pintype "bidirectional"))
    )
    (net (code "62") (name "unconnected-(CLOCK-BYP-Pad4)") (class "Default")
      (node (ref "CLOCK") (pin "4") (pinfunction "BYP_4") (pintype "bidirectional"))
    )
    (net (code "63") (name "unconnected-(LD0_SD-BYP-Pad4)") (class "Default")
      (node (ref "LD0_SD") (pin "4") (pinfunction "BYP_4") (pintype "bidirectional"))
    )
    (net (code "64") (name "unconnected-(LDO_SENSE-DNC-Pad8)") (class "Default")
      (node (ref "LDO_SENSE") (pin "8") (pinfunction "DNC_8") (pintype "no_connect"))
    )
    (net (code "65") (name "unconnected-(LDO_SENSE-DNC_2-Pad1)") (class "Default")
      (node (ref "LDO_SENSE") (pin "1") (pinfunction "DNC_2_1") (pintype "no_connect"))
    )
    (net (code "66") (name "unconnected-(LDO_SENSE-DNC_3-Pad5)") (class "Default")
      (node (ref "LDO_SENSE") (pin "5") (pinfunction "DNC_3_5") (pintype "no_connect"))
    )
    (net (code "67") (name "unconnected-(LDO_SENSE-DNC_4-Pad7)") (class "Default")
      (node (ref "LDO_SENSE") (pin "7") (pinfunction "DNC_4_7") (pintype "no_connect"))
    )
    (net (code "68") (name "unconnected-(LSHIFTD-O-Pad10)") (class "Default")
      (node (ref "LSHIFT") (pin "10") (pinfunction "O_10") (pintype "output"))
    )
    (net (code "69") (name "unconnected-(LSHIFTE-O-Pad12)") (class "Default")
      (node (ref "LSHIFT") (pin "12") (pinfunction "O_12") (pintype "output"))
    )
    (net (code "70") (name "unconnected-(LSHIFTF-O-Pad15)") (class "Default")
      (node (ref "LSHIFT") (pin "15") (pinfunction "O_15") (pintype "output"))
    )
    (net (code "71") (name "unconnected-(RTC-32KHZ-Pad1)") (class "Default")
      (node (ref "RTC") (pin "1") (pinfunction "32KHZ_1") (pintype "bidirectional"))
    )
    (net (code "72") (name "unconnected-(RTC-~{RST}-Pad4)") (class "Default")
      (node (ref "RTC") (pin "4") (pinfunction "~{RST}_4") (pintype "bidirectional"))
    )
    (net (code "73") (name "unconnected-(SD-CARD_DETECT-PadCD)") (class "Default")
      (node (ref "SD") (pin "CD") (pinfunction "CARD_DETECT_CD") (pintype "passive"))
    )
    (net (code "74") (name "unconnected-(SD-DAT1-Pad8)") (class "Default")
      (node (ref "SD") (pin "8") (pinfunction "DAT1_8") (pintype "bidirectional"))
    )
    (net (code "75") (name "unconnected-(SD-DAT2-Pad9)") (class "Default")
      (node (ref "SD") (pin "9") (pinfunction "DAT2_9") (pintype "bidirectional"))
    )
    (net (code "76") (name "unconnected-(SD-WRITE_PROTECT-PadWP)") (class "Default")
      (node (ref "SD") (pin "WP") (pinfunction "WRITE_PROTECT_WP") (pintype "passive"))
    )
    (net (code "77") (name "unconnected-(U2-CBUS0-Pad15)") (class "Default")
      (node (ref "U2") (pin "15") (pinfunction "CBUS0_15") (pintype "bidirectional"))
    )
    (net (code "78") (name "unconnected-(U2-CBUS3-Pad16)") (class "Default")
      (node (ref "U2") (pin "16") (pinfunction "CBUS3_16") (pintype "bidirectional"))
    )
    (net (code "79") (name "unconnected-(U2-DCD#-Pad5)") (class "Default")
      (node (ref "U2") (pin "5") (pinfunction "DCD#_5") (pintype "bidirectional"))
    )
    (net (code "80") (name "unconnected-(U2-DSR#-Pad4)") (class "Default")
      (node (ref "U2") (pin "4") (pinfunction "DSR#_4") (pintype "bidirectional"))
    )
    (net (code "81") (name "unconnected-(U2-RI#-Pad2)") (class "Default")
      (node (ref "U2") (pin "2") (pinfunction "RI#_2") (pintype "bidirectional"))
    )
    (net (code "82") (name "unconnected-(U2-RTS#-Pad19)") (class "Default")
      (node (ref "U2") (pin "19") (pinfunction "RTS#_19") (pintype "bidirectional"))
    )
  )
)
